# 10ACurrentSensor.net
KiCad netlist of a schematic drawn in Altium Designer
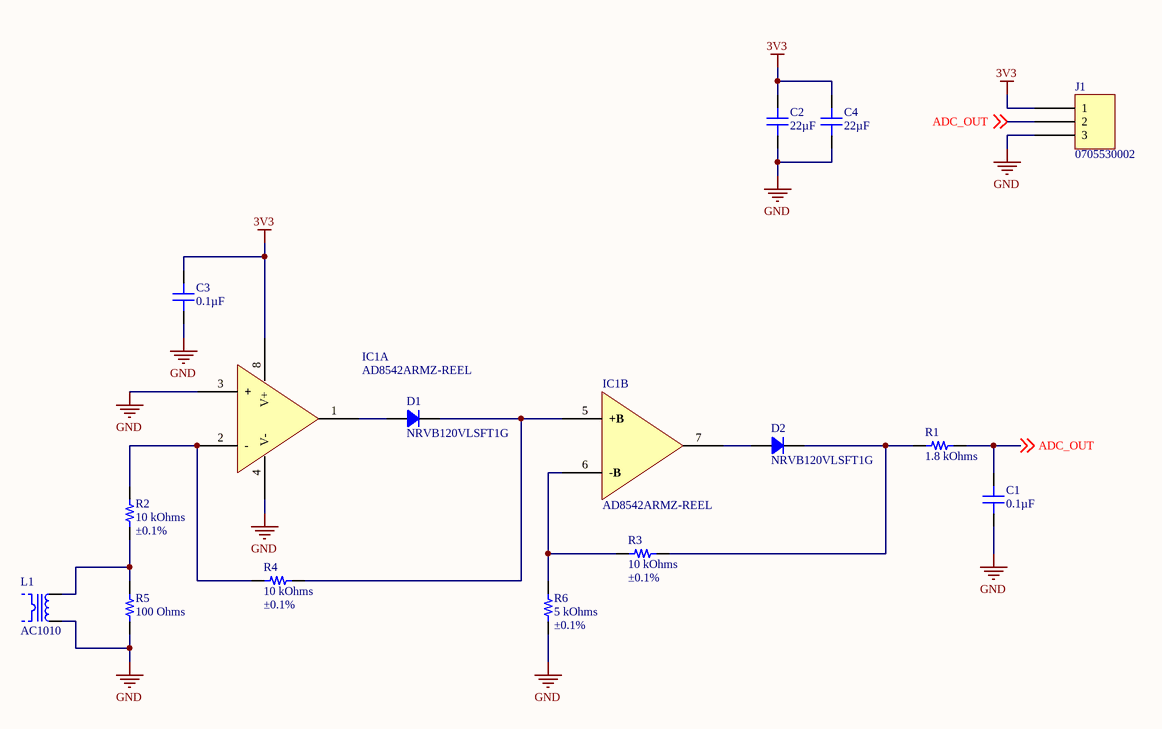
[diagram p0: 10ACurrentSensor.SchDoc]

(export (version "E")
  (design (tool "Eeschema 10.0.6"))
  (components
    (comp (ref "C1")
      (value "0.1µF")
      (footprint "CAP 0603_1608")
      (description "CAP CER 0.1UF 16V X7R 0603")
      (fields (field (name "PART NUMBER") "CS0603KRX7R7BB104") (field (name "MANUFACTURER") "Yageo"))
      (libsource (lib "Celestial Altium Library - altium_library") (part "Capacitor"))
    )
    (comp (ref "C2")
      (value "22µF")
      (footprint "CAP 1206_3216 - 1.0MM")
      (description "CAP CER 22UF 16V X5R 1206")
      (fields
        (field (name "PART NUMBER") "CL31A226MOCLNNC")
        (field (name "MANUFACTURER") "Samsung Electro-Mechanics")
      )
      (libsource (lib "Celestial Altium Library - altium_library") (part "Capacitor"))
    )
    (comp (ref "C3")
      (value "0.1µF")
      (footprint "CAP 0603_1608")
      (description "CAP CER 0.1UF 16V X7R 0603")
      (fields (field (name "PART NUMBER") "CS0603KRX7R7BB104") (field (name "MANUFACTURER") "Yageo"))
      (libsource (lib "Celestial Altium Library - altium_library") (part "Capacitor"))
    )
    (comp (ref "C4")
      (value "22µF")
      (footprint "CAP 1206_3216 - 1.0MM")
      (description "CAP CER 22UF 16V X5R 1206")
      (fields
        (field (name "PART NUMBER") "CL31A226MOCLNNC")
        (field (name "MANUFACTURER") "Samsung Electro-Mechanics")
      )
      (libsource (lib "Celestial Altium Library - altium_library") (part "Capacitor"))
    )
    (comp (ref "D1")
      (value "NRVB120VLSFT1G")
      (footprint "SOD123F")
      (description "DIODE SCHOTTKY 20V 1A SOD123")
      (fields (field (name "MANUFACTURER") "ON Semiconductor"))
      (libsource (lib "Celestial Altium Library - altium_library") (part "Diode"))
    )
    (comp (ref "D2")
      (value "NRVB120VLSFT1G")
      (footprint "SOD123F")
      (description "DIODE SCHOTTKY 20V 1A SOD123")
      (fields (field (name "MANUFACTURER") "ON Semiconductor"))
      (libsource (lib "Celestial Altium Library - altium_library") (part "Diode"))
    )
    (comp (ref "IC1")
      (value "AD8542ARMZ-REEL")
      (footprint "ANALOG MSOP-8 RM-8")
      (description "IC OPAMP GP 2 CIRCUIT 8MSOP")
      (fields (field (name "MANUFACTURER") "Analog Devices Inc."))
      (libsource (lib "Celestial Altium Library - altium_library") (part "ANALOG DEV AD8542"))
    )
    (comp (ref "J1")
      (value "0705530002")
      (footprint "MOLEX SDA-70553-3PIN")
      (description "CONN HEADER R/A 3POS 2.54MM")
      (fields (field (name "MANUFACTURER") "Molex"))
      (libsource (lib "Celestial Altium Library - altium_library") (part "3 Pin"))
    )
    (comp (ref "L1")
      (value "AC1010")
      (footprint "TALEMA AC1010")
      (description "CURR SENSE XFMR 10A T/H")
      (fields (field (name "MANUFACTURER") "Talema Group LLC"))
      (libsource (lib "Celestial Altium Library - altium_library") (part "TALEMA AC1xxx"))
    )
    (comp (ref "R1")
      (value "1.8 kOhms")
      (footprint "RES 0603_1608")
      (description "RES 1.8K OHM 5% 1/10W 0603")
      (fields
        (field (name "PART NUMBER") "RMCF0603JT1K80")
        (field (name "MANUFACTURER") "Stackpole Electronics Inc")
      )
      (libsource (lib "Celestial Altium Library - altium_library") (part "Resistor"))
    )
    (comp (ref "R2")
      (value "10 kOhms")
      (footprint "RES 0603_1608")
      (description "RES SMD 10K OHM 0.1% 1/10W 0603")
      (fields
        (field (name "PART NUMBER") "ERA-3AEB103V")
        (field (name "MANUFACTURER") "Panasonic Electronic Components")
        (field (name "TOLERANCE") "±0.1%")
      )
      (libsource (lib "Celestial Altium Library - altium_library") (part "Resistor"))
    )
    (comp (ref "R3")
      (value "10 kOhms")
      (footprint "RES 0603_1608")
      (description "RES SMD 10K OHM 0.1% 1/10W 0603")
      (fields
        (field (name "PART NUMBER") "ERA-3AEB103V")
        (field (name "MANUFACTURER") "Panasonic Electronic Components")
        (field (name "TOLERANCE") "±0.1%")
      )
      (libsource (lib "Celestial Altium Library - altium_library") (part "Resistor"))
    )
    (comp (ref "R4")
      (value "10 kOhms")
      (footprint "RES 0603_1608")
      (description "RES SMD 10K OHM 0.1% 1/10W 0603")
      (fields
        (field (name "PART NUMBER") "ERA-3AEB103V")
        (field (name "MANUFACTURER") "Panasonic Electronic Components")
        (field (name "TOLERANCE") "±0.1%")
      )
      (libsource (lib "Celestial Altium Library - altium_library") (part "Resistor"))
    )
    (comp (ref "R5")
      (value "100 Ohms")
      (footprint "RES 0603_1608")
      (description "RES SMD 100 OHM 5% 1/4W 0603")
      (fields (field (name "PART NUMBER") "ESR03EZPJ101") (field (name "MANUFACTURER") "Rohm Semiconductor"))
      (libsource (lib "Celestial Altium Library - altium_library") (part "Resistor"))
    )
    (comp (ref "R6")
      (value "5 kOhms")
      (footprint "RES 0603_1608")
      (description "RES SMD 5K OHM 0.1% 0.15W 0603")
      (fields
        (field (name "PART NUMBER") "PNM0603E5001BST5")
        (field (name "MANUFACTURER") "Vishay Thin Film")
        (field (name "TOLERANCE") "±0.1%")
      )
      (libsource (lib "Celestial Altium Library - altium_library") (part "Resistor"))
    )
  )
  (nets
    (net (code "1") (name "3V3") (class "Default")
      (node (ref "C2") (pin "2") (pinfunction "2_2") (pintype "passive"))
      (node (ref "C3") (pin "2") (pinfunction "2_2") (pintype "passive"))
      (node (ref "C4") (pin "2") (pinfunction "2_2") (pintype "passive"))
      (node (ref "IC1") (pin "8") (pinfunction "V+_8") (pintype "passive"))
      (node (ref "J1") (pin "1") (pinfunction "1_1") (pintype "passive"))
    )
    (net (code "2") (name "ADC_OUT") (class "Default")
      (node (ref "C1") (pin "2") (pinfunction "2_2") (pintype "passive"))
      (node (ref "J1") (pin "2") (pinfunction "2_2") (pintype "passive"))
      (node (ref "R1") (pin "2") (pinfunction "2_2") (pintype "passive"))
    )
    (net (code "3") (name "GND") (class "Default")
      (node (ref "C1") (pin "1") (pinfunction "1_1") (pintype "passive"))
      (node (ref "C2") (pin "1") (pinfunction "1_1") (pintype "passive"))
      (node (ref "C3") (pin "1") (pinfunction "1_1") (pintype "passive"))
      (node (ref "C4") (pin "1") (pinfunction "1_1") (pintype "passive"))
      (node (ref "IC1") (pin "3") (pinfunction "+_3") (pintype "passive"))
      (node (ref "IC1") (pin "4") (pinfunction "V-_4") (pintype "passive"))
      (node (ref "J1") (pin "3") (pinfunction "3_3") (pintype "passive"))
      (node (ref "L1") (pin "1") (pinfunction "1_1") (pintype "passive"))
      (node (ref "R5") (pin "1") (pinfunction "1_1") (pintype "passive"))
      (node (ref "R6") (pin "2") (pinfunction "2_2") (pintype "passive"))
    )
    (net (code "4") (name "Net-(D2-Pad2)") (class "Default")
      (node (ref "D2") (pin "2") (pinfunction "2_2") (pintype "passive"))
      (node (ref "R1") (pin "1") (pinfunction "1_1") (pintype "passive"))
      (node (ref "R3") (pin "1") (pinfunction "1_1") (pintype "passive"))
    )
    (net (code "5") (name "Net-(IC1A--)") (class "Default")
      (node (ref "IC1") (pin "2") (pinfunction "-_2") (pintype "passive"))
      (node (ref "R2") (pin "2") (pinfunction "2_2") (pintype "passive"))
      (node (ref "R4") (pin "2") (pinfunction "2_2") (pintype "passive"))
    )
    (net (code "6") (name "Net-(IC1A-OUT)") (class "Default")
      (node (ref "D1") (pin "1") (pinfunction "1_1") (pintype "passive"))
      (node (ref "IC1") (pin "1") (pinfunction "OUT_1") (pintype "passive"))
    )
    (net (code "7") (name "Net-(IC1B-+B)") (class "Default")
      (node (ref "D1") (pin "2") (pinfunction "2_2") (pintype "passive"))
      (node (ref "IC1") (pin "5") (pinfunction "+B_5") (pintype "passive"))
      (node (ref "R4") (pin "1") (pinfunction "1_1") (pintype "passive"))
    )
    (net (code "8") (name "Net-(IC1B--B)") (class "Default")
      (node (ref "IC1") (pin "6") (pinfunction "-B_6") (pintype "passive"))
      (node (ref "R3") (pin "2") (pinfunction "2_2") (pintype "passive"))
      (node (ref "R6") (pin "1") (pinfunction "1_1") (pintype "passive"))
    )
    (net (code "9") (name "Net-(IC1B-OUT_B)") (class "Default")
      (node (ref "D2") (pin "1") (pinfunction "1_1") (pintype "passive"))
      (node (ref "IC1") (pin "7") (pinfunction "OUT_B_7") (pintype "passive"))
    )
    (net (code "10") (name "Net-(L1-Pad2)") (class "Default")
      (node (ref "L1") (pin "2") (pinfunction "2_2") (pintype "passive"))
      (node (ref "R2") (pin "1") (pinfunction "1_1") (pintype "passive"))
      (node (ref "R5") (pin "2") (pinfunction "2_2") (pintype "passive"))
    )
  )
)
